# Power.net
KiCad netlist of a schematic drawn in Altium Designer
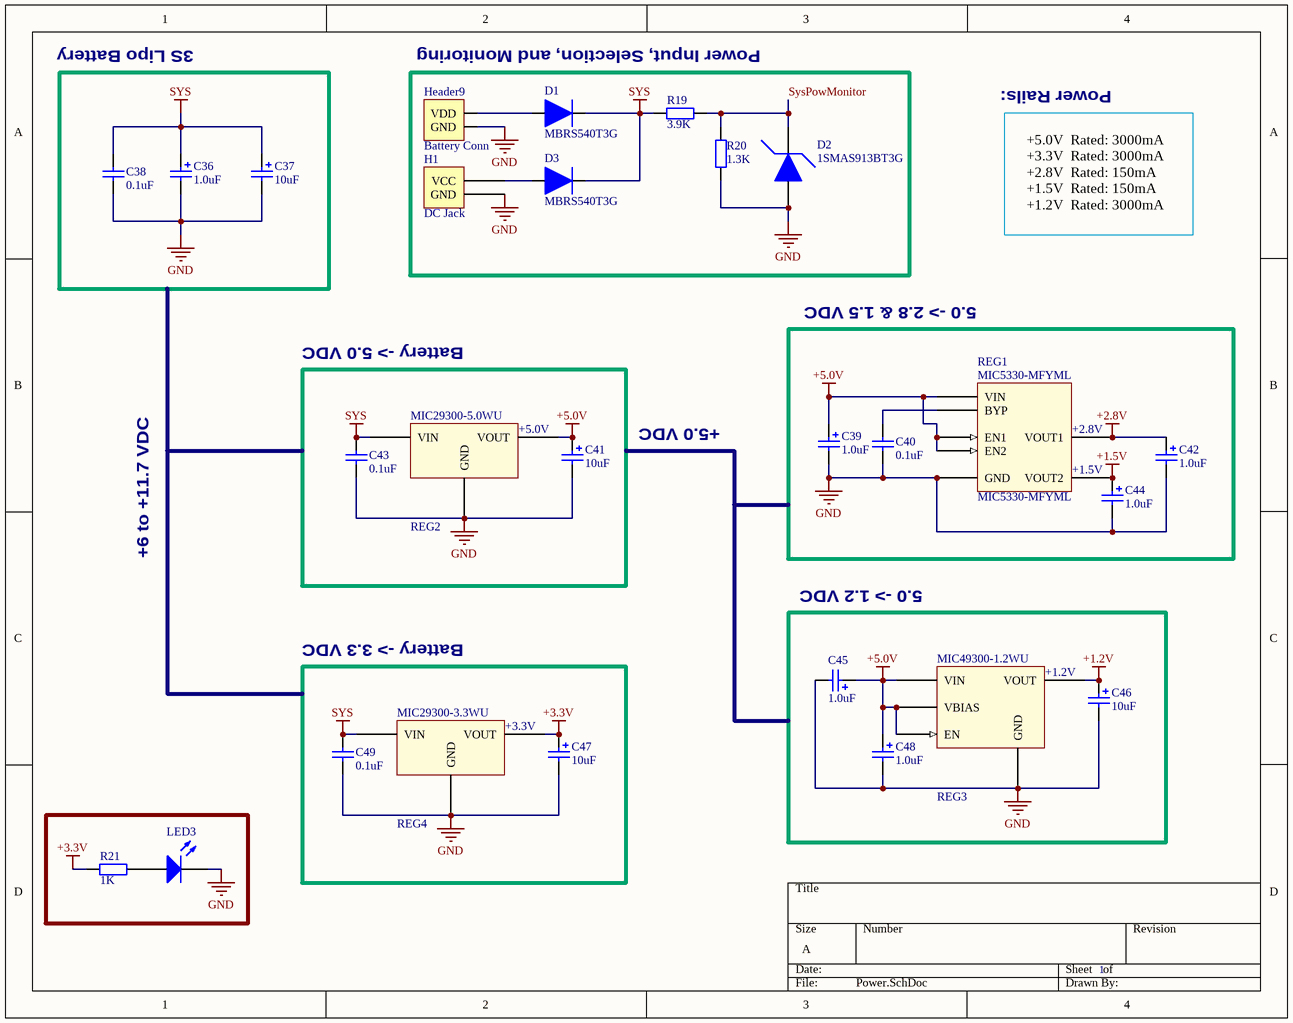
[diagram p0: Power.SchDoc]

(export (version "E")
  (design (tool "Eeschema 10.0.6"))
  (components
    (comp (ref "C36")
      (value "1.0uF")
      (footprint "CAPPR2-5x5")
      (description "Polarized Capacitor (Radial)")
      (fields (field (name "Comment") "1.0uF Electrolitic") (field (name "PUBLISHER") "Altium Limited"))
      (libsource (lib "Miscellaneous Devices") (part "Cap Pol1"))
    )
    (comp (ref "C37")
      (value "10uF")
      (footprint "CAPPR2-5x5")
      (description "Polarized Capacitor (Radial)")
      (fields (field (name "Comment") "10uF Electrolitic") (field (name "PUBLISHER") "Altium Limited"))
      (libsource (lib "Miscellaneous Devices") (part "Cap Pol1"))
    )
    (comp (ref "C38")
      (value "0.1uF")
      (footprint "CAPRD5-6.5x4.5")
      (description "Capacitor")
      (fields (field (name "Comment") "0.1uF Ceramic"))
      (libsource (lib "Miscellaneous Devices") (part "Cap"))
    )
    (comp (ref "C39")
      (value "1.0uF")
      (footprint "Capacitor - Tantalum Case A")
      (description "Tantalum Capacitor - Case A")
      (fields (field (name "Comment") "1.0uF Low-ESR Tantalum CaseA"))
      (libsource (lib "Ad-Flier_Parts") (part "SMD_Cap_Tantalum"))
    )
    (comp (ref "C40")
      (value "0.1uF")
      (footprint "SMD 1206")
      (description "Capacitor")
      (fields (field (name "Comment") "0.1uF SMD 1206"))
      (libsource (lib "Miscellaneous Devices") (part "Cap"))
    )
    (comp (ref "C41")
      (value "10uF")
      (footprint "Capacitor - Tantalum Case A")
      (description "Tantalum Capacitor - Case A")
      (fields (field (name "Comment") "10uF Low-ESR Tantalum CaseA"))
      (libsource (lib "Ad-Flier_Parts") (part "SMD_Cap_Tantalum"))
    )
    (comp (ref "C42")
      (value "1.0uF")
      (footprint "Capacitor - Tantalum Case A")
      (description "Tantalum Capacitor - Case A")
      (fields (field (name "Comment") "1.0uF Low-ESR Tantalum CaseA"))
      (libsource (lib "Ad-Flier_Parts") (part "SMD_Cap_Tantalum"))
    )
    (comp (ref "C43")
      (value "0.1uF")
      (footprint "SMD 1206")
      (description "Capacitor")
      (fields (field (name "Comment") "0.1uF SMD 1206"))
      (libsource (lib "Miscellaneous Devices") (part "Cap"))
    )
    (comp (ref "C44")
      (value "1.0uF")
      (footprint "Capacitor - Tantalum Case A")
      (description "Tantalum Capacitor - Case A")
      (fields (field (name "Comment") "1.0uF Low-ESR Tantalum CaseA"))
      (libsource (lib "Ad-Flier_Parts") (part "SMD_Cap_Tantalum"))
    )
    (comp (ref "C45")
      (value "1.0uF")
      (footprint "Capacitor - Tantalum Case A")
      (description "Tantalum Capacitor - Case A")
      (fields (field (name "Comment") "1.0uF Low-ESR Tantalum CaseA"))
      (libsource (lib "Ad-Flier_Parts") (part "SMD_Cap_Tantalum"))
    )
    (comp (ref "C46")
      (value "10uF")
      (footprint "Capacitor - Tantalum Case A")
      (description "Tantalum Capacitor - Case A")
      (fields (field (name "Comment") "10uF Low-ESR Tantalum CaseA"))
      (libsource (lib "Ad-Flier_Parts") (part "SMD_Cap_Tantalum"))
    )
    (comp (ref "C47")
      (value "10uF")
      (footprint "Capacitor - Tantalum Case A")
      (description "Tantalum Capacitor - Case A")
      (fields (field (name "Comment") "10uF Low-ESR Tantalum CaseA"))
      (libsource (lib "Ad-Flier_Parts") (part "SMD_Cap_Tantalum"))
    )
    (comp (ref "C48")
      (value "1.0uF")
      (footprint "Capacitor - Tantalum Case A")
      (description "Tantalum Capacitor - Case A")
      (fields (field (name "Comment") "1.0uF Low-ESR Tantalum CaseA"))
      (libsource (lib "Ad-Flier_Parts") (part "SMD_Cap_Tantalum"))
    )
    (comp (ref "C49")
      (value "0.1uF")
      (footprint "SMD 1206")
      (description "Capacitor")
      (fields (field (name "Comment") "0.1uF SMD 1206"))
      (libsource (lib "Miscellaneous Devices") (part "Cap"))
    )
    (comp (ref "D1")
      (value "MBRS540T3G")
      (footprint "MBRS540T3G")
      (description "40V 5A Scottky Diode")
      (libsource (lib "Ad-Flier_Parts") (part "MBRS540T3G"))
    )
    (comp (ref "D2")
      (value "1SMAS913BT3G")
      (footprint "1SMA5913BT3G")
      (description "3.3V 1.5W Zener Diode")
      (libsource (lib "Ad-Flier_Parts") (part "1SMAS913BT3G"))
    )
    (comp (ref "D3")
      (value "MBRS540T3G")
      (footprint "MBRS540T3G")
      (description "40V 5A Scottky Diode")
      (libsource (lib "Ad-Flier_Parts") (part "MBRS540T3G"))
    )
    (comp (ref "H1")
      (value "DC Jack")
      (footprint "DC Power Jack")
      (description "DC Power Jack")
      (libsource (lib "Ad-Flier_Parts") (part "DC Jack"))
    )
    (comp (ref "Header9")
      (value "Battery Conn")
      (footprint "PC Wire Connector")
      (libsource (lib "Ad-Flier_Parts") (part "PC Wire Connector"))
    )
    (comp (ref "LED3")
      (value "LED PLCC-4")
      (footprint "PLCC-4 LED")
      (description "Surface Mount Chip LED")
      (libsource (lib "Ad-Flier_Parts") (part "LED PLCC-4"))
    )
    (comp (ref "R19")
      (value "3.9K")
      (footprint "RES12.2-8.5X3.3")
      (description "Resistor")
      (fields (field (name "Comment") "3.9K Radial"))
      (libsource (lib "") (part "Res2_1"))
    )
    (comp (ref "R20")
      (value "1.3K")
      (footprint "RES12.2-8.5X3.3")
      (description "Resistor")
      (fields (field (name "Comment") "1.3K Radial"))
      (libsource (lib "Miscellaneous Devices") (part "Res2"))
    )
    (comp (ref "R21")
      (value "1K")
      (footprint "SMD 0805")
      (description "Resistor")
      (fields (field (name "Comment") "1K SMD 0805"))
      (libsource (lib "") (part "Res2_1"))
    )
    (comp (ref "REG1")
      (value "MIC5330-MFYML")
      (footprint "MIC5330-MFYML TR")
      (description "Dual 300mA LDO (Lead Free Compliant)")
      (libsource (lib "Micrel Parts") (part "MIC5330-MFYML"))
    )
    (comp (ref "REG2")
      (value "MIC29300-5.0WU")
      (footprint "TO-263 D2PACK")
      (description "3.0A LDO Fixed Volt.(ROHS Compliant)")
      (libsource (lib "Micrel Parts") (part "MIC29300-5.0WU"))
    )
    (comp (ref "REG3")
      (value "MIC49300-1.2WR")
      (footprint "MIC49300-1.2WR SPACK-5")
      (description "Dual Supply, LV 3.0A LDO(ROHS Compliant)")
      (libsource (lib "Micrel Parts") (part "MIC49300-1.2WR"))
    )
    (comp (ref "REG4")
      (value "MIC29300-3.3WU")
      (footprint "TO-263 D2PACK")
      (description "3.0A LDO Fixed Volt.(ROHS Compliant)")
      (libsource (lib "Micrel Parts") (part "MIC29300-3.3WU"))
    )
  )
  (nets
    (net (code "1") (name "+1.2V") (class "Default")
      (node (ref "C46") (pin "1") (pinfunction "+_1") (pintype "passive"))
      (node (ref "REG3") (pin "4") (pinfunction "VOUT_4") (pintype "power_in"))
    )
    (net (code "2") (name "+1.5V") (class "Default")
      (node (ref "C44") (pin "1") (pinfunction "+_1") (pintype "passive"))
      (node (ref "REG1") (pin "6") (pinfunction "VOUT2_6") (pintype "power_in"))
    )
    (net (code "3") (name "+2.8V") (class "Default")
      (node (ref "C42") (pin "1") (pinfunction "+_1") (pintype "passive"))
      (node (ref "REG1") (pin "7") (pinfunction "VOUT1_7") (pintype "power_in"))
    )
    (net (code "4") (name "+3.3V") (class "Default")
      (node (ref "C47") (pin "1") (pinfunction "+_1") (pintype "passive"))
      (node (ref "R21") (pin "2") (pinfunction "2_2") (pintype "passive"))
      (node (ref "REG4") (pin "2") (pinfunction "VOUT_2") (pintype "power_in"))
    )
    (net (code "5") (name "+5.0V") (class "Default")
      (node (ref "C39") (pin "1") (pinfunction "+_1") (pintype "passive"))
      (node (ref "C41") (pin "1") (pinfunction "+_1") (pintype "passive"))
      (node (ref "C45") (pin "1") (pinfunction "+_1") (pintype "passive"))
      (node (ref "C48") (pin "1") (pinfunction "+_1") (pintype "passive"))
      (node (ref "REG1") (pin "0") (pinfunction "VIN_0") (pintype "power_in"))
      (node (ref "REG1") (pin "3") (pinfunction "EN2_3") (pintype "input"))
      (node (ref "REG1") (pin "4") (pinfunction "EN1_4") (pintype "input"))
      (node (ref "REG2") (pin "2") (pinfunction "VOUT_2") (pintype "power_in"))
      (node (ref "REG3") (pin "0") (pinfunction "EN_0") (pintype "input"))
      (node (ref "REG3") (pin "1") (pinfunction "VBIAS_1") (pintype "power_in"))
      (node (ref "REG3") (pin "3") (pinfunction "VIN_3") (pintype "power_in"))
    )
    (net (code "6") (name "/SysPowMonitor") (class "Default")
      (node (ref "D2") (pin "1") (pinfunction "Out_1") (pintype "passive"))
      (node (ref "R19") (pin "1") (pinfunction "1_1") (pintype "passive"))
      (node (ref "R20") (pin "2") (pinfunction "2_2") (pintype "passive"))
    )
    (net (code "7") (name "GND") (class "Default")
      (node (ref "C36") (pin "2") (pinfunction "2_2") (pintype "passive"))
      (node (ref "C37") (pin "2") (pinfunction "2_2") (pintype "passive"))
      (node (ref "C38") (pin "1") (pinfunction "1_1") (pintype "passive"))
      (node (ref "C39") (pin "2") (pinfunction "-_2") (pintype "passive"))
      (node (ref "C40") (pin "1") (pinfunction "1_1") (pintype "passive"))
      (node (ref "C41") (pin "2") (pinfunction "-_2") (pintype "passive"))
      (node (ref "C42") (pin "2") (pinfunction "-_2") (pintype "passive"))
      (node (ref "C43") (pin "2") (pinfunction "2_2") (pintype "passive"))
      (node (ref "C44") (pin "2") (pinfunction "-_2") (pintype "passive"))
      (node (ref "C45") (pin "2") (pinfunction "-_2") (pintype "passive"))
      (node (ref "C46") (pin "2") (pinfunction "-_2") (pintype "passive"))
      (node (ref "C47") (pin "2") (pinfunction "-_2") (pintype "passive"))
      (node (ref "C48") (pin "2") (pinfunction "-_2") (pintype "passive"))
      (node (ref "C49") (pin "1") (pinfunction "1_1") (pintype "passive"))
      (node (ref "D2") (pin "0") (pinfunction "In_0") (pintype "passive"))
      (node (ref "H1") (pin "GND") (pinfunction "GND_GND") (pintype "passive"))
      (node (ref "Header9") (pin "R") (pinfunction "GND_R") (pintype "passive"))
      (node (ref "LED3") (pin "2") (pinfunction "K_2") (pintype "passive"))
      (node (ref "R20") (pin "1") (pinfunction "1_1") (pintype "passive"))
      (node (ref "REG1") (pin "1") (pinfunction "GND_1") (pintype "power_in"))
      (node (ref "REG2") (pin "1") (pinfunction "GND_1") (pintype "power_in"))
      (node (ref "REG3") (pin "2") (pinfunction "GND_2") (pintype "power_in"))
      (node (ref "REG4") (pin "1") (pinfunction "GND_1") (pintype "power_in"))
    )
    (net (code "8") (name "Net-(D1-In)") (class "Default")
      (node (ref "D1") (pin "0") (pinfunction "In_0") (pintype "passive"))
      (node (ref "Header9") (pin "L") (pinfunction "VDD_L") (pintype "passive"))
    )
    (net (code "9") (name "Net-(D3-In)") (class "Default")
      (node (ref "D3") (pin "0") (pinfunction "In_0") (pintype "passive"))
      (node (ref "H1") (pin "VCC") (pinfunction "VCC_VCC") (pintype "passive"))
    )
    (net (code "10") (name "Net-(LED3-A)") (class "Default")
      (node (ref "LED3") (pin "1") (pinfunction "A_1") (pintype "passive"))
      (node (ref "R21") (pin "1") (pinfunction "1_1") (pintype "passive"))
    )
    (net (code "11") (name "Net-(REG1-BYP)") (class "Default")
      (node (ref "C40") (pin "2") (pinfunction "2_2") (pintype "passive"))
      (node (ref "REG1") (pin "2") (pinfunction "BYP_2") (pintype "power_in"))
    )
    (net (code "12") (name "SYS") (class "Default")
      (node (ref "C36") (pin "1") (pinfunction "1_1") (pintype "passive"))
      (node (ref "C37") (pin "1") (pinfunction "1_1") (pintype "passive"))
      (node (ref "C38") (pin "2") (pinfunction "2_2") (pintype "passive"))
      (node (ref "C43") (pin "1") (pinfunction "1_1") (pintype "passive"))
      (node (ref "C49") (pin "2") (pinfunction "2_2") (pintype "passive"))
      (node (ref "D1") (pin "1") (pinfunction "Out_1") (pintype "passive"))
      (node (ref "D3") (pin "1") (pinfunction "Out_1") (pintype "passive"))
      (node (ref "R19") (pin "2") (pinfunction "2_2") (pintype "passive"))
      (node (ref "REG2") (pin "0") (pinfunction "VIN_0") (pintype "power_in"))
      (node (ref "REG4") (pin "0") (pinfunction "VIN_0") (pintype "power_in"))
    )
    (net (code "13") (name "unconnected-(H1-PadNC)") (class "Default")
      (node (ref "H1") (pin "NC") (pinfunction "NC_NC") (pintype "passive"))
    )
    (net (code "14") (name "unconnected-(REG1-NC-Pad5)") (class "Default")
      (node (ref "REG1") (pin "5") (pinfunction "NC_5") (pintype "passive"))
    )
  )
)
